# Antenna.net
KiCad netlist of a schematic drawn in Altium Designer
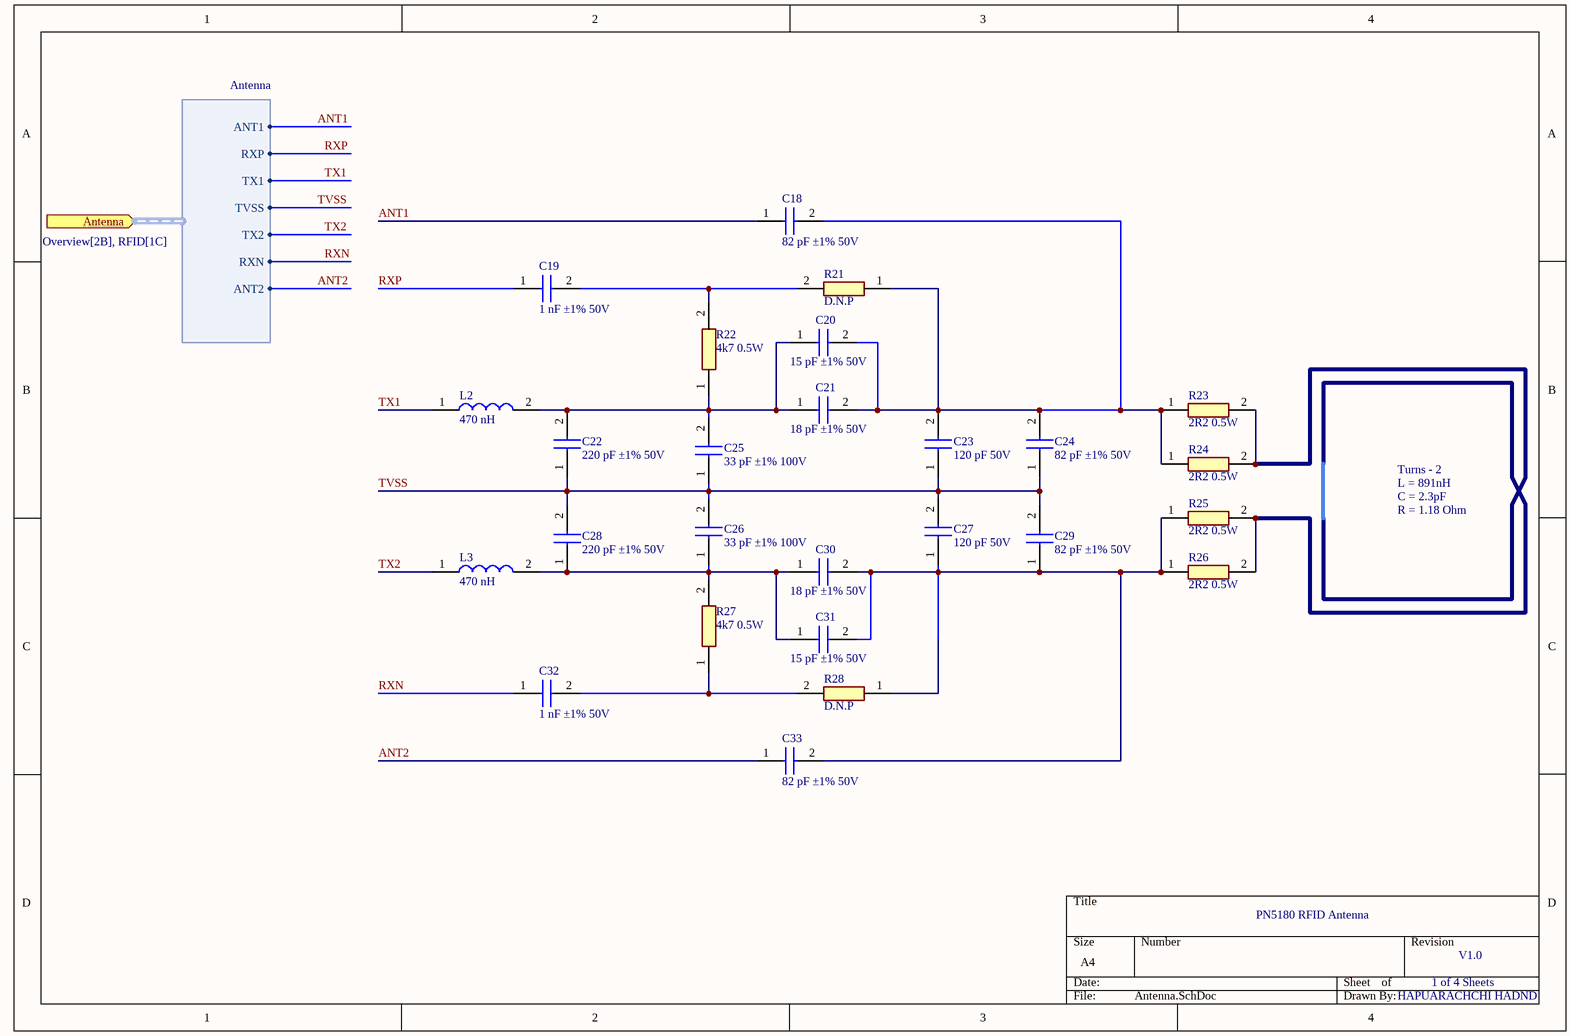
[diagram p0: Antenna.SchDoc]

(export (version "E")
  (design (tool "Eeschema 10.0.6"))
  (components
    (comp (ref "C18")
      (value "82 pF ±1% 50V")
      (footprint "Antenna_Order:CAPC2012X94N_1")
      (description "82 pF ±1% 50V Ceramic Capacitor C0G, NP0 0805 (2012 Metric)")
      (fields
        (field (name "MANUFACTURER_PART_NUMBER") "08055A820FAT2A")
        (field (name "MOUSER PART NUMBER") "581-08055A820FAT2A")
      )
      (libsource (lib "Antenna_Order") (part "82pF"))
    )
    (comp (ref "C19")
      (value "1 nF ±1% 50V")
      (footprint "Antenna_Order:CAPC2012X90N")
      (description "1 nF ±1% 50V Ceramic Capacitor C0G, NP0 0805 (2012 Metric)")
      (fields
        (field (name "MANUFACTURER_PART_NUMBER") "VJ0805A102FXACW1BC")
        (field (name "MOUSER PART NUMBER") "77-VJ0805A102FXACBC")
      )
      (libsource (lib "Antenna_Order") (part "1nF"))
    )
    (comp (ref "C20")
      (value "15 pF ±1% 50V")
      (footprint "Antenna_Order:C0805")
      (description "15 pF ±1% 50V Ceramic Capacitor C0G, NP0 0805 (2012 Metric)")
      (fields
        (field (name "MANUFACTURER_PART_NUMBER") "C0805C150F5GACTU")
        (field (name "MOUSER PART NUMBER") "80-C0805C150F5GACTU")
      )
      (libsource (lib "Antenna_Order") (part "15pF"))
    )
    (comp (ref "C21")
      (value "18 pF ±1% 50V")
      (footprint "Antenna_Order:CAPC2012X94N_2")
      (description "18 pF ±1% 50V Ceramic Capacitor C0G, NP0 0805 (2012 Metric)")
      (fields
        (field (name "MANUFACTURER_PART_NUMBER") "08055A180FAT2A")
        (field (name "MOUSER PART NUMBER") "581-08055A180FAT2A")
      )
      (libsource (lib "Antenna_Order") (part "18pF"))
    )
    (comp (ref "C22")
      (value "220 pF ±1% 50V")
      (footprint "Antenna_Order:CAPC2012X94N_3")
      (description "220 pF ±1% 50V Ceramic Capacitor C0G, NP0 0805 (2012 Metric)")
      (fields
        (field (name "MANUFACTURER_PART_NUMBER") "08055A221FAT2A")
        (field (name "MOUSER PART NUMBER") "581-08055A221FAT2A")
      )
      (libsource (lib "Antenna_Order") (part "220pF"))
    )
    (comp (ref "C23")
      (value "120 pF 50V")
      (footprint "Antenna_Order:CAPC2012X94N_5")
      (description "120 pF ±1% 50V Ceramic Capacitor C0G, NP0 0805 (2012 Metric)")
      (fields
        (field (name "MANUFACTURER_PART_NUMBER") "08055A121FAT2A")
        (field (name "MOUSER PART NUMBER") "581-08055A121F")
      )
      (libsource (lib "Antenna_Order") (part "120pF"))
    )
    (comp (ref "C24")
      (value "82 pF ±1% 50V")
      (footprint "Antenna_Order:CAPC2012X94N_1")
      (description "82 pF ±1% 50V Ceramic Capacitor C0G, NP0 0805 (2012 Metric)")
      (fields
        (field (name "MANUFACTURER_PART_NUMBER") "08055A820FAT2A")
        (field (name "MOUSER PART NUMBER") "581-08055A820FAT2A")
      )
      (libsource (lib "Antenna_Order") (part "82pF"))
    )
    (comp (ref "C25")
      (value "33 pF ±1% 100V")
      (footprint "Antenna_Order:CAPC2012X94N_4")
      (description "33 pF ±1% 100V Ceramic Capacitor C0G, NP0 0805 (2012 Metric)")
      (fields
        (field (name "MANUFACTURER_PART_NUMBER") "08051A330FAT2A")
        (field (name "MOUSER PART NUMBER") "581-08051A330F")
      )
      (libsource (lib "Antenna_Order") (part "33pF"))
    )
    (comp (ref "C26")
      (value "33 pF ±1% 100V")
      (footprint "Antenna_Order:CAPC2012X94N_4")
      (description "33 pF ±1% 100V Ceramic Capacitor C0G, NP0 0805 (2012 Metric)")
      (fields
        (field (name "MANUFACTURER_PART_NUMBER") "08051A330FAT2A")
        (field (name "MOUSER PART NUMBER") "581-08051A330F")
      )
      (libsource (lib "Antenna_Order") (part "33pF"))
    )
    (comp (ref "C27")
      (value "120 pF 50V")
      (footprint "Antenna_Order:CAPC2012X94N_5")
      (description "120 pF ±1% 50V Ceramic Capacitor C0G, NP0 0805 (2012 Metric)")
      (fields
        (field (name "MANUFACTURER_PART_NUMBER") "08055A121FAT2A")
        (field (name "MOUSER PART NUMBER") "581-08055A121F")
      )
      (libsource (lib "Antenna_Order") (part "120pF"))
    )
    (comp (ref "C28")
      (value "220 pF ±1% 50V")
      (footprint "Antenna_Order:CAPC2012X94N_3")
      (description "220 pF ±1% 50V Ceramic Capacitor C0G, NP0 0805 (2012 Metric)")
      (fields
        (field (name "MANUFACTURER_PART_NUMBER") "08055A221FAT2A")
        (field (name "MOUSER PART NUMBER") "581-08055A221FAT2A")
      )
      (libsource (lib "Antenna_Order") (part "220pF"))
    )
    (comp (ref "C29")
      (value "82 pF ±1% 50V")
      (footprint "Antenna_Order:CAPC2012X94N_1")
      (description "82 pF ±1% 50V Ceramic Capacitor C0G, NP0 0805 (2012 Metric)")
      (fields
        (field (name "MANUFACTURER_PART_NUMBER") "08055A820FAT2A")
        (field (name "MOUSER PART NUMBER") "581-08055A820FAT2A")
      )
      (libsource (lib "Antenna_Order") (part "82pF"))
    )
    (comp (ref "C30")
      (value "18 pF ±1% 50V")
      (footprint "Antenna_Order:CAPC2012X94N_2")
      (description "18 pF ±1% 50V Ceramic Capacitor C0G, NP0 0805 (2012 Metric)")
      (fields
        (field (name "MANUFACTURER_PART_NUMBER") "08055A180FAT2A")
        (field (name "MOUSER PART NUMBER") "581-08055A180FAT2A")
      )
      (libsource (lib "Antenna_Order") (part "18pF"))
    )
    (comp (ref "C31")
      (value "15 pF ±1% 50V")
      (footprint "Antenna_Order:C0805")
      (description "15 pF ±1% 50V Ceramic Capacitor C0G, NP0 0805 (2012 Metric)")
      (fields
        (field (name "MANUFACTURER_PART_NUMBER") "C0805C150F5GACTU")
        (field (name "MOUSER PART NUMBER") "80-C0805C150F5GACTU")
      )
      (libsource (lib "Antenna_Order") (part "15pF"))
    )
    (comp (ref "C32")
      (value "1 nF ±1% 50V")
      (footprint "Antenna_Order:CAPC2012X90N")
      (description "1 nF ±1% 50V Ceramic Capacitor C0G, NP0 0805 (2012 Metric)")
      (fields
        (field (name "MANUFACTURER_PART_NUMBER") "VJ0805A102FXACW1BC")
        (field (name "MOUSER PART NUMBER") "77-VJ0805A102FXACBC")
      )
      (libsource (lib "Antenna_Order") (part "1nF"))
    )
    (comp (ref "C33")
      (value "82 pF ±1% 50V")
      (footprint "Antenna_Order:CAPC2012X94N_1")
      (description "82 pF ±1% 50V Ceramic Capacitor C0G, NP0 0805 (2012 Metric)")
      (fields
        (field (name "MANUFACTURER_PART_NUMBER") "08055A820FAT2A")
        (field (name "MOUSER PART NUMBER") "581-08055A820FAT2A")
      )
      (libsource (lib "Antenna_Order") (part "82pF"))
    )
    (comp (ref "L2")
      (value "470 nH")
      (footprint "Antenna_Order:INDC1608X95N")
      (description "470 nH Shielded Multilayer Inductor 400 mA 494mOhm Max 0603 (1608 Metric)")
      (fields
        (field (name "MANUFACTURER_PART_NUMBER") "MLJ1608WR47JT000")
        (field (name "MOUSER PART NUMBER") "810-MLJ1608WR47JT000")
      )
      (libsource (lib "Antenna_Order") (part "470nH"))
    )
    (comp (ref "L3")
      (value "470 nH")
      (footprint "Antenna_Order:INDC1608X95N")
      (description "470 nH Shielded Multilayer Inductor 400 mA 494mOhm Max 0603 (1608 Metric)")
      (fields
        (field (name "MANUFACTURER_PART_NUMBER") "MLJ1608WR47JT000")
        (field (name "MOUSER PART NUMBER") "810-MLJ1608WR47JT000")
      )
      (libsource (lib "Antenna_Order") (part "470nH"))
    )
    (comp (ref "R21")
      (value "D.N.P")
      (footprint "Antenna_Order:RESC2012X60N_1")
      (fields
        (field (name "MANUFACTURER_PART_NUMBER") "CRCW08054K70FKEAHP")
        (field (name "MOUSER PART NUMBER") "71-CRCW08054K70FKEAH")
      )
      (libsource (lib "") (part "4k7Ohm_0805_1"))
    )
    (comp (ref "R22")
      (value "4k7 0.5W")
      (footprint "Antenna_Order:RESC2012X60N_1")
      (fields
        (field (name "MANUFACTURER_PART_NUMBER") "CRCW08054K70FKEAHP")
        (field (name "MOUSER PART NUMBER") "71-CRCW08054K70FKEAH")
      )
      (libsource (lib "Antenna_Order") (part "4k7Ohm_0805"))
    )
    (comp (ref "R23")
      (value "2R2 0.5W")
      (footprint "Antenna_Order:RESC2012X60N_2")
      (fields
        (field (name "MANUFACTURER_PART_NUMBER") "CRCW08052R20FKEAHP")
        (field (name "MOUSER PART NUMBER") "71-CRCW08052R20FKEAH")
      )
      (libsource (lib "Antenna_Order") (part "2.2Ohm"))
    )
    (comp (ref "R24")
      (value "2R2 0.5W")
      (footprint "Antenna_Order:RESC2012X60N_2")
      (fields
        (field (name "MANUFACTURER_PART_NUMBER") "CRCW08052R20FKEAHP")
        (field (name "MOUSER PART NUMBER") "71-CRCW08052R20FKEAH")
      )
      (libsource (lib "Antenna_Order") (part "2.2Ohm"))
    )
    (comp (ref "R25")
      (value "2R2 0.5W")
      (footprint "Antenna_Order:RESC2012X60N_2")
      (fields
        (field (name "MANUFACTURER_PART_NUMBER") "CRCW08052R20FKEAHP")
        (field (name "MOUSER PART NUMBER") "71-CRCW08052R20FKEAH")
      )
      (libsource (lib "Antenna_Order") (part "2.2Ohm"))
    )
    (comp (ref "R26")
      (value "2R2 0.5W")
      (footprint "Antenna_Order:RESC2012X60N_2")
      (fields
        (field (name "MANUFACTURER_PART_NUMBER") "CRCW08052R20FKEAHP")
        (field (name "MOUSER PART NUMBER") "71-CRCW08052R20FKEAH")
      )
      (libsource (lib "Antenna_Order") (part "2.2Ohm"))
    )
    (comp (ref "R27")
      (value "4k7 0.5W")
      (footprint "Antenna_Order:RESC2012X60N_1")
      (fields
        (field (name "MANUFACTURER_PART_NUMBER") "CRCW08054K70FKEAHP")
        (field (name "MOUSER PART NUMBER") "71-CRCW08054K70FKEAH")
      )
      (libsource (lib "Antenna_Order") (part "4k7Ohm_0805"))
    )
    (comp (ref "R28")
      (value "D.N.P")
      (footprint "Antenna_Order:RESC2012X60N_1")
      (fields
        (field (name "MANUFACTURER_PART_NUMBER") "CRCW08054K70FKEAHP")
        (field (name "MOUSER PART NUMBER") "71-CRCW08054K70FKEAH")
      )
      (libsource (lib "") (part "4k7Ohm_0805_1"))
    )
  )
  (nets
    (net (code "2") (name "/ANT1") (class "Default")
      (node (ref "C18") (pin "1") (pinfunction "1_1") (pintype "passive"))
    )
    (net (code "3") (name "/ANT2") (class "Default")
      (node (ref "C33") (pin "1") (pinfunction "1_1") (pintype "passive"))
    )
    (net (code "4") (name "/RXN") (class "Default")
      (node (ref "C32") (pin "1") (pinfunction "1_1") (pintype "passive"))
    )
    (net (code "5") (name "/RXP") (class "Default")
      (node (ref "C19") (pin "1") (pinfunction "1_1") (pintype "passive"))
    )
    (net (code "6") (name "/TVSS") (class "Default")
      (node (ref "C22") (pin "1") (pinfunction "1_1") (pintype "passive"))
      (node (ref "C23") (pin "1") (pinfunction "1_1") (pintype "passive"))
      (node (ref "C24") (pin "1") (pinfunction "1_1") (pintype "passive"))
      (node (ref "C25") (pin "1") (pinfunction "1_1") (pintype "passive"))
      (node (ref "C26") (pin "2") (pinfunction "2_2") (pintype "passive"))
      (node (ref "C27") (pin "2") (pinfunction "2_2") (pintype "passive"))
      (node (ref "C28") (pin "2") (pinfunction "2_2") (pintype "passive"))
      (node (ref "C29") (pin "2") (pinfunction "2_2") (pintype "passive"))
    )
    (net (code "7") (name "/TX1") (class "Default")
      (node (ref "L2") (pin "1") (pinfunction "1_1") (pintype "passive"))
    )
    (net (code "8") (name "/TX2") (class "Default")
      (node (ref "L3") (pin "1") (pinfunction "1_1") (pintype "passive"))
    )
    (net (code "10") (name "Net-(C18-Pad2)") (class "Default")
      (node (ref "C18") (pin "2") (pinfunction "2_2") (pintype "passive"))
      (node (ref "C20") (pin "2") (pinfunction "2_2") (pintype "passive"))
      (node (ref "C21") (pin "2") (pinfunction "2_2") (pintype "passive"))
      (node (ref "C23") (pin "2") (pinfunction "2_2") (pintype "passive"))
      (node (ref "C24") (pin "2") (pinfunction "2_2") (pintype "passive"))
      (node (ref "R21") (pin "1") (pinfunction "1_1") (pintype "passive"))
      (node (ref "R23") (pin "1") (pinfunction "1_1") (pintype "passive"))
      (node (ref "R24") (pin "1") (pinfunction "1_1") (pintype "passive"))
    )
    (net (code "11") (name "Net-(C19-Pad2)") (class "Default")
      (node (ref "C19") (pin "2") (pinfunction "2_2") (pintype "passive"))
      (node (ref "R21") (pin "2") (pinfunction "2_2") (pintype "passive"))
      (node (ref "R22") (pin "2") (pinfunction "2_2") (pintype "passive"))
    )
    (net (code "12") (name "Net-(C20-Pad1)") (class "Default")
      (node (ref "C20") (pin "1") (pinfunction "1_1") (pintype "passive"))
      (node (ref "C21") (pin "1") (pinfunction "1_1") (pintype "passive"))
      (node (ref "C22") (pin "2") (pinfunction "2_2") (pintype "passive"))
      (node (ref "C25") (pin "2") (pinfunction "2_2") (pintype "passive"))
      (node (ref "L2") (pin "2") (pinfunction "2_2") (pintype "passive"))
      (node (ref "R22") (pin "1") (pinfunction "1_1") (pintype "passive"))
    )
    (net (code "13") (name "Net-(C26-Pad1)") (class "Default")
      (node (ref "C26") (pin "1") (pinfunction "1_1") (pintype "passive"))
      (node (ref "C28") (pin "1") (pinfunction "1_1") (pintype "passive"))
      (node (ref "C30") (pin "1") (pinfunction "1_1") (pintype "passive"))
      (node (ref "C31") (pin "1") (pinfunction "1_1") (pintype "passive"))
      (node (ref "L3") (pin "2") (pinfunction "2_2") (pintype "passive"))
      (node (ref "R27") (pin "2") (pinfunction "2_2") (pintype "passive"))
    )
    (net (code "14") (name "Net-(C27-Pad1)") (class "Default")
      (node (ref "C27") (pin "1") (pinfunction "1_1") (pintype "passive"))
      (node (ref "C29") (pin "1") (pinfunction "1_1") (pintype "passive"))
      (node (ref "C30") (pin "2") (pinfunction "2_2") (pintype "passive"))
      (node (ref "C31") (pin "2") (pinfunction "2_2") (pintype "passive"))
      (node (ref "C33") (pin "2") (pinfunction "2_2") (pintype "passive"))
      (node (ref "R25") (pin "1") (pinfunction "1_1") (pintype "passive"))
      (node (ref "R26") (pin "1") (pinfunction "1_1") (pintype "passive"))
      (node (ref "R28") (pin "1") (pinfunction "1_1") (pintype "passive"))
    )
    (net (code "15") (name "Net-(C32-Pad2)") (class "Default")
      (node (ref "C32") (pin "2") (pinfunction "2_2") (pintype "passive"))
      (node (ref "R27") (pin "1") (pinfunction "1_1") (pintype "passive"))
      (node (ref "R28") (pin "2") (pinfunction "2_2") (pintype "passive"))
    )
    (net (code "16") (name "Net-(R23-Pad2)") (class "Default")
      (node (ref "R23") (pin "2") (pinfunction "2_2") (pintype "passive"))
      (node (ref "R24") (pin "2") (pinfunction "2_2") (pintype "passive"))
      (node (ref "R25") (pin "2") (pinfunction "2_2") (pintype "passive"))
      (node (ref "R26") (pin "2") (pinfunction "2_2") (pintype "passive"))
    )
  )
)
